# PowerSupply.net
KiCad netlist of a schematic drawn in Altium Designer
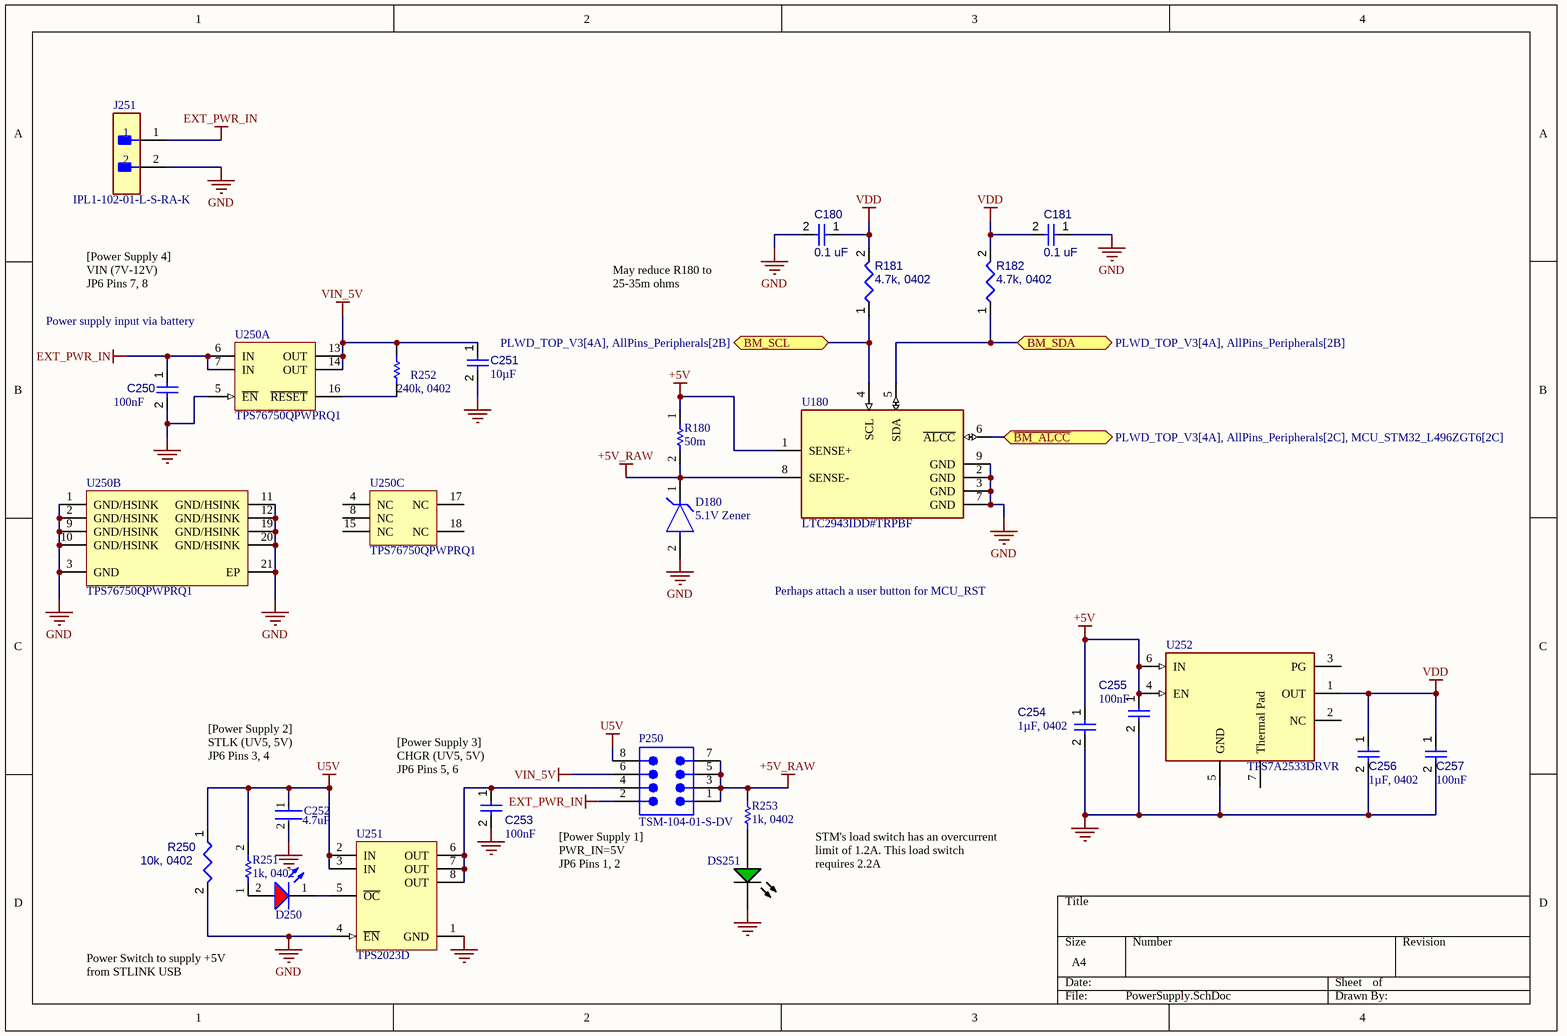
[diagram p0: PowerSupply.SchDoc]

(export (version "E")
  (design (tool "Eeschema 10.0.6"))
  (components
    (comp (ref "C180")
      (value "0.1 uF")
      (footprint "CAPC1005X56X25LL10T15")
      (description "Chip Capacitor, 0.1 uF, +/- 5%, 16 V, 0402 (1005 Metric)")
      (fields (field (name "TOLERANCE") "5%"))
      (libsource (lib "Carleton University") (part "CAP-NP-2"))
    )
    (comp (ref "C181")
      (value "0.1 uF")
      (footprint "CAPC1005X56X25LL10T15")
      (description "Chip Capacitor, 0.1 uF, +/- 5%, 16 V, 0402 (1005 Metric)")
      (fields (field (name "TOLERANCE") "5%"))
      (libsource (lib "Carleton University") (part "CAP-NP-2"))
    )
    (comp (ref "C250")
      (value "100nF")
      (footprint "CAPC1005X56X25LL10T15")
      (description "Chip Capacitor, 0.1 uF, +/- 5%, 16 V, 0402 (1005 Metric)")
      (fields (field (name "TOLERANCE") "5%") (field (name "Comment") "Capacitor 0.1 uF +/- 5% 16 V 0402"))
      (libsource (lib "Carleton University") (part "CAP-NP-2"))
    )
    (comp (ref "C251")
      (value "10µF")
      (footprint "CAPC0603(1608)100_L")
      (description "Chip Capacitor, 10µF +/-20%, 10V, 0603, Thickness 1 mm")
      (fields (field (name "TOLERANCE") "10%") (field (name "Comment") "Capacitor 10µF +/-20% 10V 0603"))
      (libsource (lib "Carleton University") (part "CAP-NP-2"))
    )
    (comp (ref "C252")
      (value "CL05A475MP5NRNC")
      (footprint "FP-CL282-IPC_C")
      (description "Cap Ceramic 4.7uF 10V X5R ±20% SMD 0402 +85°C Paper T/R")
      (fields (field (name "CAPACITANCE") "4.7uF") (field (name "TOLERANCE") "20%"))
      (libsource (lib "Altium Content Vault") (part "b4654b650e69147ec39a6b967a45e02"))
    )
    (comp (ref "C253")
      (value "100nF")
      (footprint "CAPC1005X56X25LL10T15")
      (description "Chip Capacitor, 0.1 uF, +/- 5%, 16 V, 0402 (1005 Metric)")
      (fields (field (name "TOLERANCE") "5%") (field (name "Comment") "Capacitor 0.1 uF +/- 5% 16 V 0402"))
      (libsource (lib "Carleton University") (part "CAP-NP-2"))
    )
    (comp (ref "C254")
      (value "1µF, 0402")
      (footprint "CAPC0402(1005)60_L")
      (description "Chip Capacitor, 1µF +/-20%, 10V, 0402, Thickness 0.6 mm")
      (fields (field (name "TOLERANCE") "10%") (field (name "Comment") "Capacitor 1µF +/-20% 10V 0402"))
      (libsource (lib "Carleton University") (part "CAP-NP-2"))
    )
    (comp (ref "C255")
      (value "100nF")
      (footprint "CAPC1005X56X25LL10T15")
      (description "Chip Capacitor, 0.1 uF, +/- 5%, 16 V, 0402 (1005 Metric)")
      (fields (field (name "TOLERANCE") "5%") (field (name "Comment") "Capacitor 0.1 uF +/- 5% 16 V 0402"))
      (libsource (lib "Carleton University") (part "CAP-NP-2"))
    )
    (comp (ref "C256")
      (value "1µF, 0402")
      (footprint "CAPC0402(1005)60_L")
      (description "Chip Capacitor, 1µF +/-20%, 10V, 0402, Thickness 0.6 mm")
      (fields (field (name "TOLERANCE") "10%") (field (name "Comment") "Capacitor 1µF +/-20% 10V 0402"))
      (libsource (lib "Carleton University") (part "CAP-NP-2"))
    )
    (comp (ref "C257")
      (value "100nF")
      (footprint "CAPC1005X56X25LL10T15")
      (description "Chip Capacitor, 0.1 uF, +/- 5%, 16 V, 0402 (1005 Metric)")
      (fields (field (name "TOLERANCE") "5%") (field (name "Comment") "Capacitor 0.1 uF +/- 5% 16 V 0402"))
      (libsource (lib "Carleton University") (part "CAP-NP-2"))
    )
    (comp (ref "D180")
      (value "5.1V Zener")
      (footprint "FP-SOD123-MFG")
      (description "DIODE ZENER 5.1V 500MW SOD123")
      (fields
        (field (name "MANUFACTURER PART NUMBER") "BZT52C5V1-7-F")
        (field (name "OCTOPART") "https://octopart.com/bzt52c5v1-7-f-diodes+inc.-326718")
      )
      (libsource (lib "Altium Content Vault") (part "f813f71cba58e380607f5dd3caf9714"))
    )
    (comp (ref "D250")
      (value "150120SS75000")
      (footprint "WL-SMCW_1206_150120xx75000")
      (libsource (lib "Altium Content Vault") (part "LED_Red_2A-1K"))
    )
    (comp (ref "DS251")
      (value "LTST-C190GKT")
      (footprint "LTST-C190GKT_V")
      (description "LED Uni-Color Green, 100 mW, 30 mA, -55 to 85 degC, 2-Pin SMD, RoHS, Tape and Reel")
      (fields (field (name "POWER") "100mW") (field (name "MANUFACTURER") "Lite-On"))
      (libsource (lib "Carleton University") (part "LED-GREEN-AK-2"))
    )
    (comp (ref "J251")
      (value "IPL1-102-01-L-S-RA-K")
      (footprint "FP-IPL1-102-01-L-S-RA-K-0")
      (description "2 Position 1 Row .100\" (2.54 mm) pitch connector")
      (libsource (lib "Altium Content Vault") (part "1104fde15574350d21af68338faea4c"))
    )
    (comp (ref "P250")
      (value "TSM-104-01-S-DV")
      (footprint "SMTC-TSM-104-01-X-DV")
      (description "0.025\" SQ Post Header, Surface Mount, Vertical, -55 to 125 degC, 2.54 mm Pitch, 8-Pin, Male, RoHS")
      (fields (field (name "MANUFACTURER") "Samtec"))
      (libsource (lib "Altium Content Vault") (part "SMTC-TSM-104-01-X-X"))
    )
    (comp (ref "R180")
      (value "50m")
      (footprint "RESC1608X55X30NL15T15")
      (fields (field (name "MANUFACTURER") "Panasonic") (field (name "PART NUMBER") "ERJ-L03KF50MV"))
      (libsource (lib "Altium Content Vault") (part "RES"))
    )
    (comp (ref "R181")
      (value "4.7k, 0402")
      (footprint "RESC0402(1005)_L")
      (description "Chip Resistor, 4,7 kOhms, +/-1 %, 63 mW, -55 to 155 degC, 0402")
      (fields (field (name "POWER") "63mW") (field (name "TOLERANCE") "1%"))
      (libsource (lib "Carleton University") (part "RES-2"))
    )
    (comp (ref "R182")
      (value "4.7k, 0402")
      (footprint "RESC0402(1005)_L")
      (description "Chip Resistor, 4,7 kOhms, +/-1 %, 63 mW, -55 to 155 degC, 0402")
      (fields (field (name "POWER") "63mW") (field (name "TOLERANCE") "1%"))
      (libsource (lib "Carleton University") (part "RES-2"))
    )
    (comp (ref "R250")
      (value "10k, 0402")
      (footprint "RESC1005X40X25ML05T05")
      (description "Chip Resistor, 10 KOhm, +/- 1%, 0.1 W, -55 to 155 degC, 0402 (1005 Metric)")
      (fields (field (name "TOLERANCE") "1%") (field (name "POWER") "100mW"))
      (libsource (lib "Carleton University") (part "RES-2"))
    )
    (comp (ref "R251")
      (value "1k, 0402")
      (footprint "RESC1005X40X25ML05T05")
      (description "Chip Resistor, 1 KOhm, +/- 1%, 0.1 W, -55 to 155 degC, 0402 (1005 Metric)")
      (fields (field (name "POWER") "100mW") (field (name "TOLERANCE") "1%"))
      (libsource (lib "") (part "RES-2_1"))
    )
    (comp (ref "R252")
      (value "240k, 0402")
      (footprint "RESC1005X40X25NL05T05")
      (description "Chip Resistor, 240 KOhm, +/- 1%, 100 mW, -55 to 155 degC, 0402 (1005 Metric), RoHS, Tape and Reel")
      (fields (field (name "MANUFACTURER") "Basic Passives") (field (name "TOLERANCE") "1%"))
      (libsource (lib "Altium Content Vault") (part "RES-2"))
    )
    (comp (ref "R253")
      (value "1k, 0402")
      (footprint "RESC1005X40X25ML05T05")
      (description "Chip Resistor, 1 KOhm, +/- 1%, 0.1 W, -55 to 155 degC, 0402 (1005 Metric)")
      (fields (field (name "POWER") "100mW") (field (name "TOLERANCE") "1%"))
      (libsource (lib "") (part "RES-2_2"))
    )
    (comp (ref "U180")
      (value "LTC2943IDD#TRPBF")
      (footprint "FP-DD-8-05-08-1698-IPC_B")
      (description "IC BATT MONITOR MULTI-CHEM 8DFN")
      (libsource (lib "Altium Content Vault") (part "886febee6aeca4f95c872c95bb57c34"))
    )
    (comp (ref "U250")
      (value "TPS76750QPWPRQ1")
      (footprint "PWP0020L_N")
      (fields (field (name "MANUFACTURER") "Texas Instruments"))
      (libsource (lib "Altium Content Vault") (part "TI-TPS76750-Q1PWP20-2975X2000TP"))
    )
    (comp (ref "U251")
      (value "TPS2023D")
      (footprint "D0008A_M")
      (fields (field (name "MANUFACTURER") "Texas Instruments"))
      (libsource (lib "Altium Content Vault") (part "TI-TPS2023D8"))
    )
    (comp (ref "U252")
      (value "TPS7A2533DRVR")
      (footprint "FP-DRV0006A-IPC_C")
      (description "IC REG LINEAR 3.3V 300MA 6WSON")
      (libsource (lib "Altium Content Vault") (part "1551be0394fee7692c532a41530f294"))
    )
  )
  (nets
    (net (code "1") (name "+5V") (class "Default")
      (node (ref "C254") (pin "1") (pinfunction "1_1") (pintype "passive"))
      (node (ref "C255") (pin "1") (pinfunction "1_1") (pintype "passive"))
      (node (ref "R180") (pin "1") (pinfunction "1_1") (pintype "passive"))
      (node (ref "U180") (pin "1") (pinfunction "SENSE+_1") (pintype "passive"))
      (node (ref "U252") (pin "4") (pinfunction "EN_4") (pintype "input"))
      (node (ref "U252") (pin "6") (pinfunction "IN_6") (pintype "input"))
    )
    (net (code "2") (name "+5V_RAW") (class "Default")
      (node (ref "D180") (pin "1") (pinfunction "C_1") (pintype "passive"))
      (node (ref "P250") (pin "1") (pinfunction "1_1") (pintype "passive"))
      (node (ref "P250") (pin "3") (pinfunction "3_3") (pintype "passive"))
      (node (ref "P250") (pin "5") (pinfunction "5_5") (pintype "passive"))
      (node (ref "P250") (pin "7") (pinfunction "7_7") (pintype "passive"))
      (node (ref "R180") (pin "2") (pinfunction "2_2") (pintype "passive"))
      (node (ref "R253") (pin "2") (pinfunction "2_2") (pintype "passive"))
      (node (ref "U180") (pin "8") (pinfunction "SENSE-_8") (pintype "passive"))
    )
    (net (code "3") (name "/BM_SCL") (class "Default")
      (node (ref "R181") (pin "1") (pinfunction "1_1") (pintype "passive"))
      (node (ref "U180") (pin "4") (pinfunction "SCL_4") (pintype "input"))
    )
    (net (code "4") (name "/BM_SDA") (class "Default")
      (node (ref "R182") (pin "1") (pinfunction "1_1") (pintype "passive"))
      (node (ref "U180") (pin "5") (pinfunction "SDA_5") (pintype "bidirectional"))
    )
    (net (code "5") (name "/~{BM_ALCC}") (class "Default")
      (node (ref "U180") (pin "6") (pinfunction "~{ALCC}_6") (pintype "bidirectional"))
    )
    (net (code "6") (name "EXT_PWR_IN") (class "Default")
      (node (ref "C250") (pin "1") (pinfunction "1_1") (pintype "passive"))
      (node (ref "J251") (pin "1") (pinfunction "1_1") (pintype "passive"))
      (node (ref "P250") (pin "2") (pinfunction "2_2") (pintype "passive"))
      (node (ref "U250") (pin "6") (pinfunction "IN_6") (pintype "power_in"))
      (node (ref "U250") (pin "7") (pinfunction "IN_7") (pintype "power_in"))
    )
    (net (code "7") (name "GND") (class "Default")
      (node (ref "C180") (pin "2") (pinfunction "2_2") (pintype "passive"))
      (node (ref "C181") (pin "1") (pinfunction "1_1") (pintype "passive"))
      (node (ref "C250") (pin "2") (pinfunction "2_2") (pintype "passive"))
      (node (ref "C251") (pin "2") (pinfunction "2_2") (pintype "passive"))
      (node (ref "C252") (pin "2") (pinfunction "2_2") (pintype "passive"))
      (node (ref "C253") (pin "2") (pinfunction "2_2") (pintype "passive"))
      (node (ref "C254") (pin "2") (pinfunction "2_2") (pintype "passive"))
      (node (ref "C255") (pin "2") (pinfunction "2_2") (pintype "passive"))
      (node (ref "C256") (pin "2") (pinfunction "2_2") (pintype "passive"))
      (node (ref "C257") (pin "2") (pinfunction "2_2") (pintype "passive"))
      (node (ref "D180") (pin "2") (pinfunction "A_2") (pintype "passive"))
      (node (ref "DS251") (pin "2") (pinfunction "K_2") (pintype "passive"))
      (node (ref "J251") (pin "2") (pinfunction "2_2") (pintype "passive"))
      (node (ref "R250") (pin "2") (pinfunction "2_2") (pintype "passive"))
      (node (ref "U180") (pin "2") (pinfunction "GND_2") (pintype "power_in"))
      (node (ref "U180") (pin "3") (pinfunction "GND_3") (pintype "power_in"))
      (node (ref "U180") (pin "7") (pinfunction "GND_7") (pintype "power_in"))
      (node (ref "U180") (pin "9") (pinfunction "GND_9") (pintype "power_in"))
      (node (ref "U250") (pin "1") (pinfunction "GND/HSINK_1") (pintype "power_in"))
      (node (ref "U250") (pin "10") (pinfunction "GND/HSINK_10") (pintype "power_in"))
      (node (ref "U250") (pin "11") (pinfunction "GND/HSINK_11") (pintype "power_in"))
      (node (ref "U250") (pin "12") (pinfunction "GND/HSINK_12") (pintype "power_in"))
      (node (ref "U250") (pin "19") (pinfunction "GND/HSINK_19") (pintype "power_in"))
      (node (ref "U250") (pin "2") (pinfunction "GND/HSINK_2") (pintype "power_in"))
      (node (ref "U250") (pin "20") (pinfunction "GND/HSINK_20") (pintype "power_in"))
      (node (ref "U250") (pin "21") (pinfunction "EP_21") (pintype "passive"))
      (node (ref "U250") (pin "3") (pinfunction "GND_3") (pintype "power_in"))
      (node (ref "U250") (pin "5") (pinfunction "~{EN}_5") (pintype "input"))
      (node (ref "U250") (pin "9") (pinfunction "GND/HSINK_9") (pintype "power_in"))
      (node (ref "U251") (pin "1") (pinfunction "GND_1") (pintype "power_in"))
      (node (ref "U251") (pin "4") (pinfunction "~{EN}_4") (pintype "input"))
      (node (ref "U252") (pin "5") (pinfunction "GND_5") (pintype "power_in"))
    )
    (net (code "8") (name "Net-(C253-Pad1)") (class "Default")
      (node (ref "C253") (pin "1") (pinfunction "1_1") (pintype "passive"))
      (node (ref "P250") (pin "4") (pinfunction "4_4") (pintype "passive"))
      (node (ref "U251") (pin "6") (pinfunction "OUT_6") (pintype "power_in"))
      (node (ref "U251") (pin "7") (pinfunction "OUT_7") (pintype "power_in"))
      (node (ref "U251") (pin "8") (pinfunction "OUT_8") (pintype "power_in"))
    )
    (net (code "9") (name "Net-(D250-A)") (class "Default")
      (node (ref "D250") (pin "2") (pinfunction "A_2") (pintype "passive"))
      (node (ref "R251") (pin "1") (pinfunction "1_1") (pintype "passive"))
    )
    (net (code "10") (name "Net-(D250-K)") (class "Default")
      (node (ref "D250") (pin "1") (pinfunction "K_1") (pintype "passive"))
      (node (ref "U251") (pin "5") (pinfunction "~{OC}_5") (pintype "open_collector"))
    )
    (net (code "11") (name "Net-(DS251-A)") (class "Default")
      (node (ref "DS251") (pin "1") (pinfunction "A_1") (pintype "passive"))
      (node (ref "R253") (pin "1") (pinfunction "1_1") (pintype "passive"))
    )
    (net (code "12") (name "Net-(U250A-~{RESET})") (class "Default")
      (node (ref "R252") (pin "1") (pinfunction "1_1") (pintype "passive"))
      (node (ref "U250") (pin "16") (pinfunction "~{RESET}_16") (pintype "tri_state"))
    )
    (net (code "13") (name "U5V") (class "Default")
      (node (ref "C252") (pin "1") (pinfunction "1_1") (pintype "passive"))
      (node (ref "P250") (pin "8") (pinfunction "8_8") (pintype "passive"))
      (node (ref "R250") (pin "1") (pinfunction "1_1") (pintype "passive"))
      (node (ref "R251") (pin "2") (pinfunction "2_2") (pintype "passive"))
      (node (ref "U251") (pin "2") (pinfunction "IN_2") (pintype "power_in"))
      (node (ref "U251") (pin "3") (pinfunction "IN_3") (pintype "power_in"))
    )
    (net (code "14") (name "VDD") (class "Default")
      (node (ref "C180") (pin "1") (pinfunction "1_1") (pintype "passive"))
      (node (ref "C181") (pin "2") (pinfunction "2_2") (pintype "passive"))
      (node (ref "C256") (pin "1") (pinfunction "1_1") (pintype "passive"))
      (node (ref "C257") (pin "1") (pinfunction "1_1") (pintype "passive"))
      (node (ref "R181") (pin "2") (pinfunction "2_2") (pintype "passive"))
      (node (ref "R182") (pin "2") (pinfunction "2_2") (pintype "passive"))
      (node (ref "U252") (pin "1") (pinfunction "OUT_1") (pintype "power_in"))
    )
    (net (code "15") (name "VIN_5V") (class "Default")
      (node (ref "C251") (pin "1") (pinfunction "1_1") (pintype "passive"))
      (node (ref "P250") (pin "6") (pinfunction "6_6") (pintype "passive"))
      (node (ref "R252") (pin "2") (pinfunction "2_2") (pintype "passive"))
      (node (ref "U250") (pin "13") (pinfunction "OUT_13") (pintype "power_in"))
      (node (ref "U250") (pin "14") (pinfunction "OUT_14") (pintype "power_in"))
    )
    (net (code "16") (name "unconnected-(U250C-NC-Pad4)") (class "Default")
      (node (ref "U250") (pin "4") (pinfunction "NC_4") (pintype "passive"))
    )
    (net (code "17") (name "unconnected-(U250C-NC-Pad8)") (class "Default")
      (node (ref "U250") (pin "8") (pinfunction "NC_8") (pintype "passive"))
    )
    (net (code "18") (name "unconnected-(U250C-NC-Pad15)") (class "Default")
      (node (ref "U250") (pin "15") (pinfunction "NC_15") (pintype "passive"))
    )
    (net (code "19") (name "unconnected-(U250C-NC-Pad17)") (class "Default")
      (node (ref "U250") (pin "17") (pinfunction "NC_17") (pintype "passive"))
    )
    (net (code "20") (name "unconnected-(U250C-NC-Pad18)") (class "Default")
      (node (ref "U250") (pin "18") (pinfunction "NC_18") (pintype "passive"))
    )
    (net (code "21") (name "unconnected-(U252-NC-Pad2)") (class "Default")
      (node (ref "U252") (pin "2") (pinfunction "NC_2") (pintype "passive"))
    )
    (net (code "22") (name "unconnected-(U252-PG-Pad3)") (class "Default")
      (node (ref "U252") (pin "3") (pinfunction "PG_3") (pintype "passive"))
    )
    (net (code "23") (name "unconnected-(U252-Thermal_Pad-Pad7)") (class "Default")
      (node (ref "U252") (pin "7") (pinfunction "Thermal_Pad_7") (pintype "power_in"))
    )
  )
)
